# SimpleFlashlightScheme.net
KiCad netlist of a schematic drawn in Altium Designer
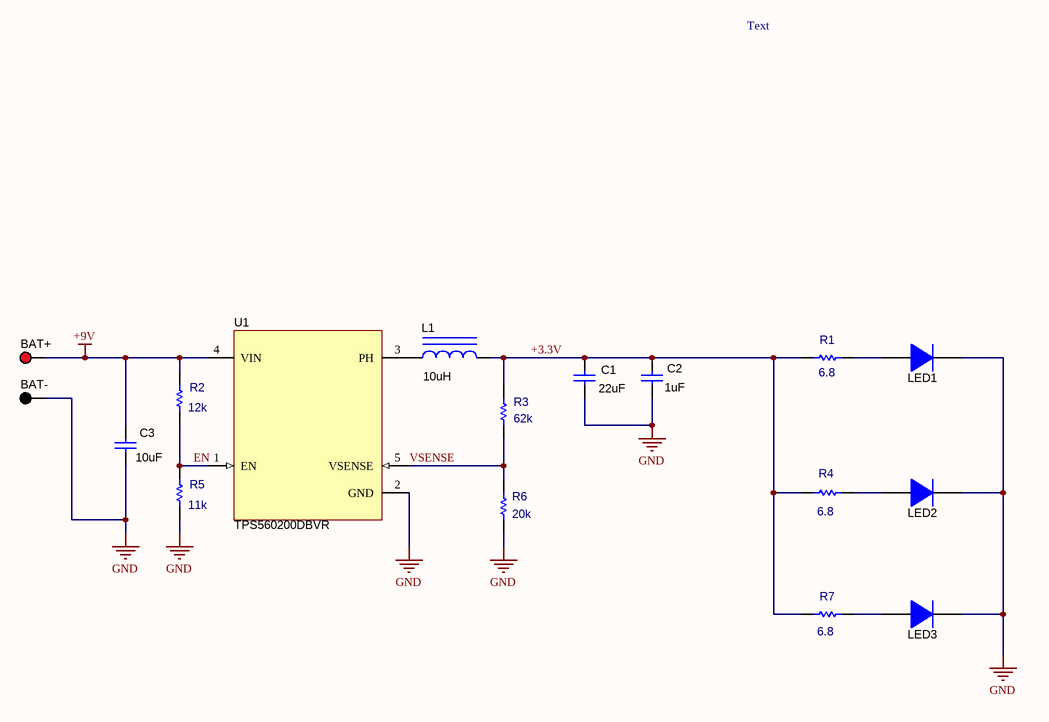
[diagram p0: SimpleFlashlightScheme.SchDoc]

(export (version "E")
  (design (tool "Eeschema 10.0.6"))
  (components
    (comp (ref "BAT+")
      (value "+")
      (footprint "KEYSTONE5000")
      (description "Power connection pad")
      (libsource (lib "SimpleFlashlight") (part "5000"))
    )
    (comp (ref "BAT-")
      (value "-")
      (footprint "KEYSTONE5000")
      (description "Power connection pad")
      (libsource (lib "SimpleFlashlight") (part "5001"))
    )
    (comp (ref "C1")
      (value "22uF")
      (footprint "1206")
      (description "Capacitor ceramic")
      (fields
        (field (name "MANUFACTURER") "MuRata")
        (field (name "MANUFACTURER PART NUMBER") "GRM31CR61C226KE15L")
      )
      (libsource (lib "SimpleFlashlight") (part "Capacitor"))
    )
    (comp (ref "C2")
      (value "1uF")
      (footprint "1206")
      (description "Capacitor ceramic")
      (fields
        (field (name "MANUFACTURER") "MuRata")
        (field (name "MANUFACTURER PART NUMBER") "GRM188R61A105K")
      )
      (libsource (lib "SimpleFlashlight") (part "Capacitor"))
    )
    (comp (ref "C3")
      (value "10uF")
      (footprint "1206")
      (description "Capacitor ceramic")
      (fields
        (field (name "MANUFACTURER") "MuRata")
        (field (name "MANUFACTURER PART NUMBER") "GRM21BR71A106KE51L")
      )
      (libsource (lib "SimpleFlashlight") (part "Capacitor"))
    )
    (comp (ref "L1")
      (value "10uH")
      (footprint "WE-PD_6033")
      (description "Inductor, Unshielded Drum Core, Metal Composite, SMD")
      (fields
        (field (name "MANUFACTURER") "Bourns")
        (field (name "MANUFACTURER PART NUMBER") "SDR0805-100ML")
      )
      (libsource (lib "SimpleFlashlight") (part "Inductor"))
    )
    (comp (ref "LED1")
      (value "4500K")
      (footprint "SimpleFlashlight:LED 2835")
      (description "SMD LED")
      (fields (field (name "MANUFACTURER") "ENLINCA") (field (name "MANUFACTURER PART NUMBER") "None"))
      (libsource (lib "SimpleFlashlight") (part "SMD LED"))
    )
    (comp (ref "LED2")
      (value "4500K")
      (footprint "SimpleFlashlight:LED 2835")
      (description "SMD LED")
      (fields (field (name "MANUFACTURER") "ENLINCA") (field (name "MANUFACTURER PART NUMBER") "None"))
      (libsource (lib "SimpleFlashlight") (part "SMD LED"))
    )
    (comp (ref "LED3")
      (value "4500K")
      (footprint "SimpleFlashlight:LED 2835")
      (description "SMD LED")
      (fields (field (name "MANUFACTURER") "ENLINCA") (field (name "MANUFACTURER PART NUMBER") "None"))
      (libsource (lib "SimpleFlashlight") (part "SMD LED"))
    )
    (comp (ref "R1")
      (value "6.8")
      (footprint "0805_HV")
      (description "Thick Film Chip Resistor")
      (fields
        (field (name "MANUFACTURER PART NUMBER") "RC0805FR-076R8L")
        (field (name "MANUFACTURER") "Yageo")
      )
      (libsource (lib "SimpleFlashlight") (part "Resistor"))
    )
    (comp (ref "R2")
      (value "12k")
      (footprint "0805_HV")
      (description "Thick Film Chip Resistor")
      (fields
        (field (name "MANUFACTURER") "Yageo")
        (field (name "MANUFACTURER PART NUMBER") "RC0805FR-0712KL")
      )
      (libsource (lib "SimpleFlashlight") (part "Resistor"))
    )
    (comp (ref "R3")
      (value "62k")
      (footprint "0805_HV")
      (description "Thick Film Chip Resistor")
      (fields
        (field (name "MANUFACTURER") "Yageo")
        (field (name "MANUFACTURER PART NUMBER") "RC0805FR-0762KL")
      )
      (libsource (lib "SimpleFlashlight") (part "Resistor"))
    )
    (comp (ref "R4")
      (value "6.8")
      (footprint "0805_HV")
      (description "Thick Film Chip Resistor")
      (fields
        (field (name "MANUFACTURER PART NUMBER") "RC0805FR-076R8L")
        (field (name "MANUFACTURER") "Yageo")
      )
      (libsource (lib "SimpleFlashlight") (part "Resistor"))
    )
    (comp (ref "R5")
      (value "11k")
      (footprint "0805_HV")
      (description "Thick Film Chip Resistor")
      (fields
        (field (name "MANUFACTURER") "Yageo")
        (field (name "MANUFACTURER PART NUMBER") "RC0805FR-0711KL")
      )
      (libsource (lib "SimpleFlashlight") (part "Resistor"))
    )
    (comp (ref "R6")
      (value "20k")
      (footprint "0805_HV")
      (description "Thick Film Chip Resistor")
      (fields
        (field (name "MANUFACTURER") "Yageo")
        (field (name "MANUFACTURER PART NUMBER") "RC0805FR-0720KL")
      )
      (libsource (lib "SimpleFlashlight") (part "Resistor"))
    )
    (comp (ref "R7")
      (value "6.8")
      (footprint "0805_HV")
      (description "Thick Film Chip Resistor")
      (fields
        (field (name "MANUFACTURER PART NUMBER") "RC0805FR-076R8L")
        (field (name "MANUFACTURER") "Yageo")
      )
      (libsource (lib "SimpleFlashlight") (part "Resistor"))
    )
    (comp (ref "U1")
      (value "TPS560200DBVR")
      (footprint "SimpleFlashlight:DBV0005A_N")
      (description "4.5V to 18V Input, 500mA Synchronous Step Down SWIFT Converter with Advanced Eco-mode, DBV0005A")
      (fields (field (name "MANUFACTURER") "Texas Instruments"))
      (libsource (lib "SimpleFlashlight") (part "TPS560200DBVR"))
    )
  )
  (nets
    (net (code "1") (name "+9V") (class "Default")
      (node (ref "BAT+") (pin "1") (pintype "passive"))
      (node (ref "C3") (pin "1") (pinfunction "1_1") (pintype "passive"))
      (node (ref "R2") (pin "2") (pinfunction "2_2") (pintype "passive"))
      (node (ref "U1") (pin "4") (pinfunction "VIN_4") (pintype "power_in"))
    )
    (net (code "2") (name "/+3.3V") (class "Default")
      (node (ref "C1") (pin "1") (pinfunction "1_1") (pintype "passive"))
      (node (ref "C2") (pin "1") (pinfunction "1_1") (pintype "passive"))
      (node (ref "L1") (pin "2") (pinfunction "2_2") (pintype "passive"))
      (node (ref "R1") (pin "1") (pinfunction "1_1") (pintype "passive"))
      (node (ref "R3") (pin "2") (pinfunction "2_2") (pintype "passive"))
      (node (ref "R4") (pin "1") (pinfunction "1_1") (pintype "passive"))
      (node (ref "R7") (pin "1") (pinfunction "1_1") (pintype "passive"))
    )
    (net (code "3") (name "/EN") (class "Default")
      (node (ref "R2") (pin "1") (pinfunction "1_1") (pintype "passive"))
      (node (ref "R5") (pin "2") (pinfunction "2_2") (pintype "passive"))
      (node (ref "U1") (pin "1") (pinfunction "EN_1") (pintype "input"))
    )
    (net (code "4") (name "/VSENSE") (class "Default")
      (node (ref "R3") (pin "1") (pinfunction "1_1") (pintype "passive"))
      (node (ref "R6") (pin "2") (pinfunction "2_2") (pintype "passive"))
      (node (ref "U1") (pin "5") (pinfunction "VSENSE_5") (pintype "input"))
    )
    (net (code "5") (name "GND") (class "Default")
      (node (ref "BAT-") (pin "1") (pintype "passive"))
      (node (ref "C1") (pin "2") (pinfunction "2_2") (pintype "passive"))
      (node (ref "C2") (pin "2") (pinfunction "2_2") (pintype "passive"))
      (node (ref "C3") (pin "2") (pinfunction "2_2") (pintype "passive"))
      (node (ref "LED1") (pin "2") (pinfunction "K_2") (pintype "passive"))
      (node (ref "LED2") (pin "2") (pinfunction "K_2") (pintype "passive"))
      (node (ref "LED3") (pin "2") (pinfunction "K_2") (pintype "passive"))
      (node (ref "R5") (pin "1") (pinfunction "1_1") (pintype "passive"))
      (node (ref "R6") (pin "1") (pinfunction "1_1") (pintype "passive"))
      (node (ref "U1") (pin "2") (pinfunction "GND_2") (pintype "power_in"))
    )
    (net (code "6") (name "Net-(LED1-A)") (class "Default")
      (node (ref "LED1") (pin "1") (pinfunction "A_1") (pintype "passive"))
      (node (ref "R1") (pin "2") (pinfunction "2_2") (pintype "passive"))
    )
    (net (code "7") (name "Net-(LED2-A)") (class "Default")
      (node (ref "LED2") (pin "1") (pinfunction "A_1") (pintype "passive"))
      (node (ref "R4") (pin "2") (pinfunction "2_2") (pintype "passive"))
    )
    (net (code "8") (name "Net-(LED3-A)") (class "Default")
      (node (ref "LED3") (pin "1") (pinfunction "A_1") (pintype "passive"))
      (node (ref "R7") (pin "2") (pinfunction "2_2") (pintype "passive"))
    )
    (net (code "9") (name "Net-(U1-PH)") (class "Default")
      (node (ref "L1") (pin "1") (pinfunction "1_1") (pintype "passive"))
      (node (ref "U1") (pin "3") (pinfunction "PH_3") (pintype "power_in"))
    )
  )
)
